# Swbot_shield.net
KiCad netlist of a schematic drawn in EAGLE
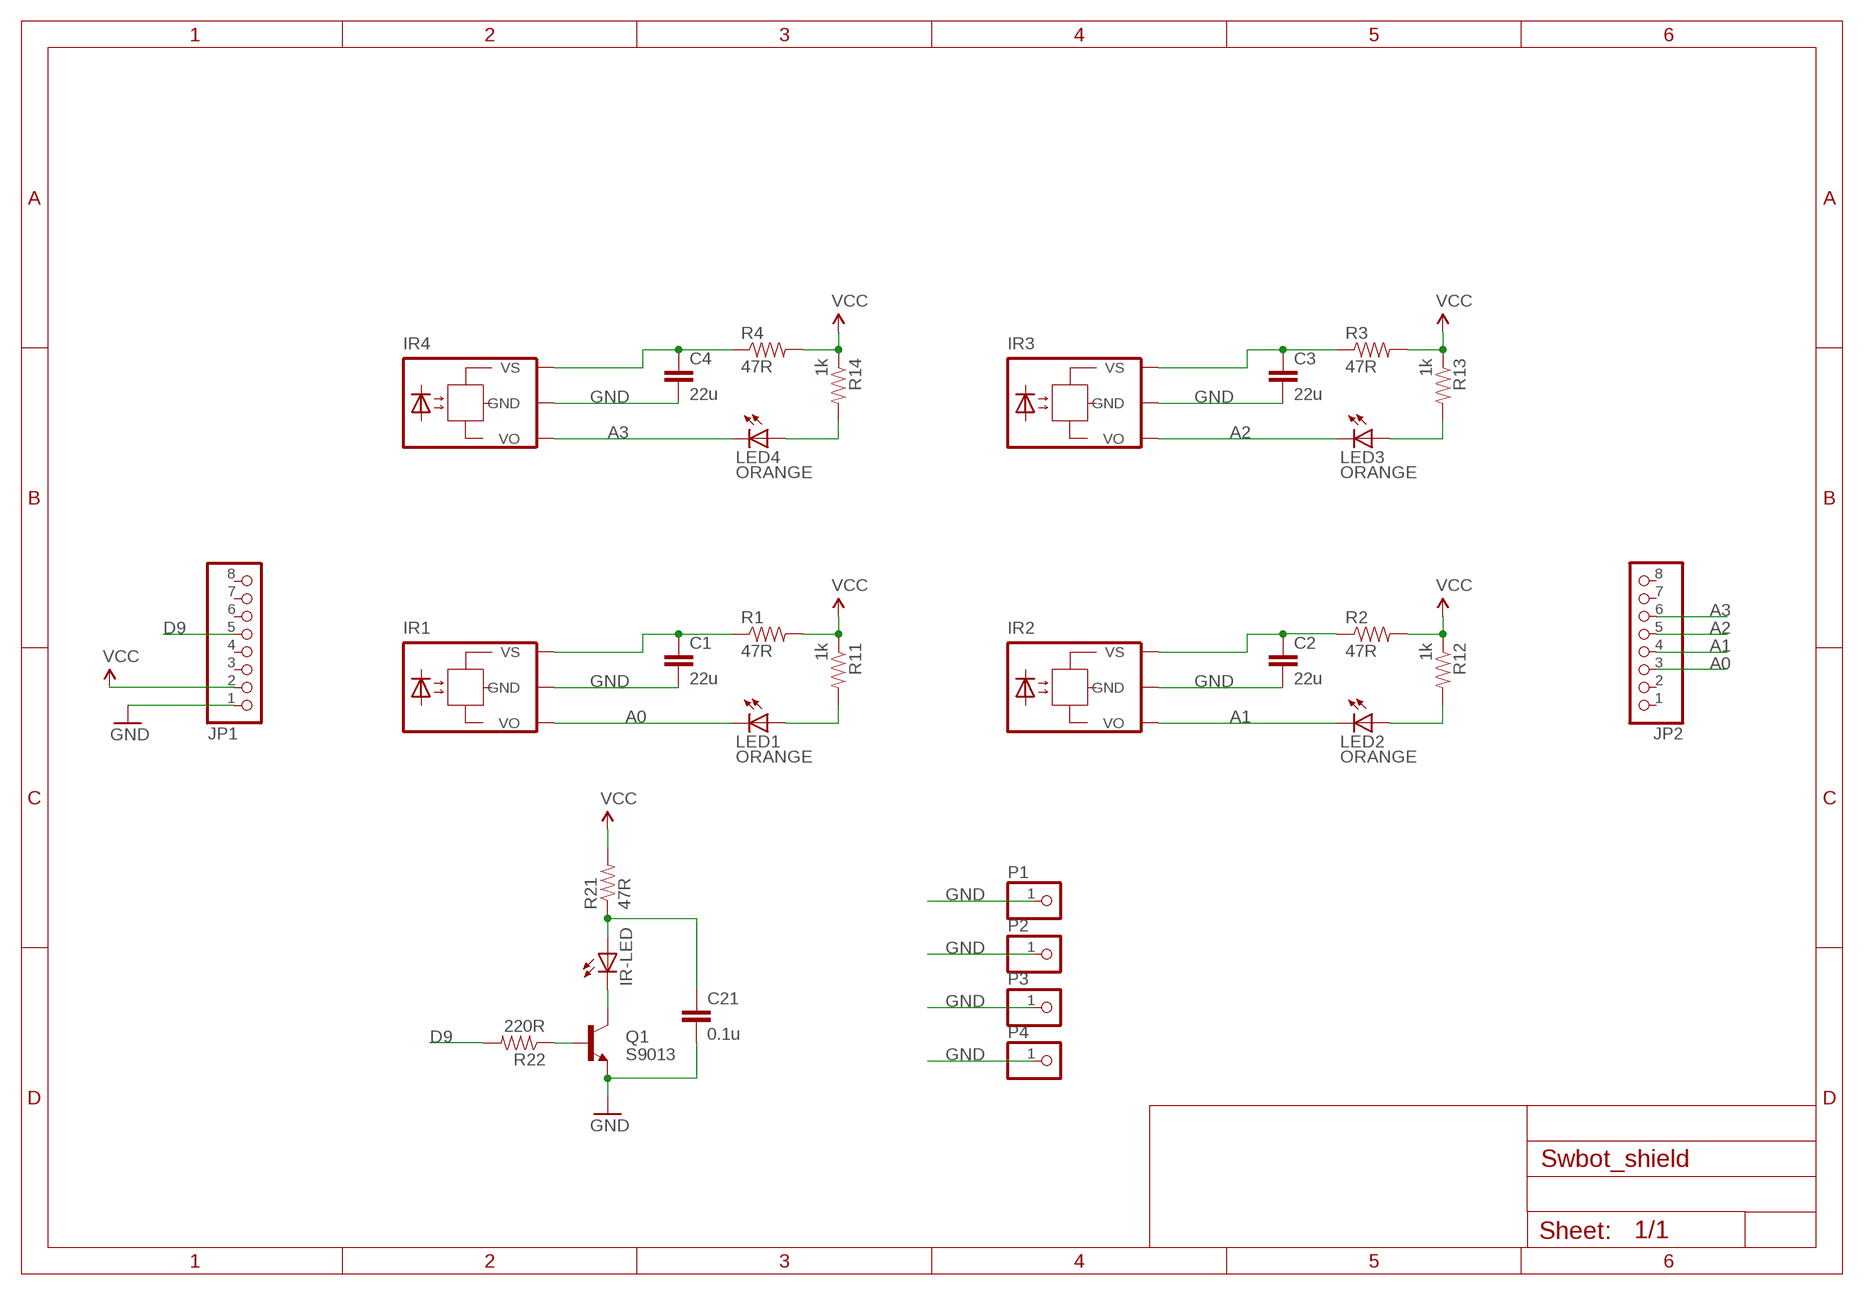
[diagram p0: schematic, sheet 1]

(export (version "E")
  (design (tool "Eeschema 10.0.6"))
  (components
    (comp (ref "C1")
      (value "22u")
      (footprint "eagle-import:1206")
      (libsource (lib "eagle-import") (part "CAP1206"))
    )
    (comp (ref "C2")
      (value "22u")
      (footprint "eagle-import:1206")
      (libsource (lib "eagle-import") (part "CAP1206"))
    )
    (comp (ref "C3")
      (value "22u")
      (footprint "eagle-import:1206")
      (libsource (lib "eagle-import") (part "CAP1206"))
    )
    (comp (ref "C4")
      (value "22u")
      (footprint "eagle-import:1206")
      (libsource (lib "eagle-import") (part "CAP1206"))
    )
    (comp (ref "C21")
      (value "0.1u")
      (footprint "eagle-import:0805")
      (libsource (lib "eagle-import") (part "CAP0805"))
    )
    (comp (ref "IR-LED")
      (value "LED5MM")
      (footprint "eagle-import:LED5MM")
      (libsource (lib "eagle-import") (part "LED5MM"))
    )
    (comp (ref "IR1")
      (value "-NJL")
      (footprint "eagle-import:TSOP")
      (libsource (lib "eagle-import") (part "?-NJL"))
    )
    (comp (ref "IR2")
      (value "-NJL")
      (footprint "eagle-import:TSOP")
      (libsource (lib "eagle-import") (part "?-NJL"))
    )
    (comp (ref "IR3")
      (value "-NJL")
      (footprint "eagle-import:TSOP")
      (libsource (lib "eagle-import") (part "?-NJL"))
    )
    (comp (ref "IR4")
      (value "-NJL")
      (footprint "eagle-import:TSOP")
      (libsource (lib "eagle-import") (part "?-NJL"))
    )
    (comp (ref "JP1")
      (value "PINHD-1X8")
      (footprint "eagle-import:1X08")
      (libsource (lib "eagle-import") (part "PINHD-1X8"))
    )
    (comp (ref "JP2")
      (value "PINHD-1X8")
      (footprint "eagle-import:1X08")
      (libsource (lib "eagle-import") (part "PINHD-1X8"))
    )
    (comp (ref "LED1")
      (value "ORANGE")
      (footprint "eagle-import:CHIPLED_0805")
      (libsource (lib "eagle-import") (part "LEDCHIPLED_0805"))
    )
    (comp (ref "LED2")
      (value "ORANGE")
      (footprint "eagle-import:CHIPLED_0805")
      (libsource (lib "eagle-import") (part "LEDCHIPLED_0805"))
    )
    (comp (ref "LED3")
      (value "ORANGE")
      (footprint "eagle-import:CHIPLED_0805")
      (libsource (lib "eagle-import") (part "LEDCHIPLED_0805"))
    )
    (comp (ref "LED4")
      (value "ORANGE")
      (footprint "eagle-import:CHIPLED_0805")
      (libsource (lib "eagle-import") (part "LEDCHIPLED_0805"))
    )
    (comp (ref "P1")
      (value "PINHD-1X1")
      (footprint "eagle-import:1X01")
      (libsource (lib "eagle-import") (part "PINHD-1X1"))
    )
    (comp (ref "P2")
      (value "PINHD-1X1")
      (footprint "eagle-import:1X01")
      (libsource (lib "eagle-import") (part "PINHD-1X1"))
    )
    (comp (ref "P3")
      (value "PINHD-1X1")
      (footprint "eagle-import:1X01")
      (libsource (lib "eagle-import") (part "PINHD-1X1"))
    )
    (comp (ref "P4")
      (value "PINHD-1X1")
      (footprint "eagle-import:1X01")
      (libsource (lib "eagle-import") (part "PINHD-1X1"))
    )
    (comp (ref "Q1")
      (value "S9013")
      (footprint "eagle-import:SOT23-3")
      (libsource (lib "eagle-import") (part "TRANSISTOR_NPNSOT23-3"))
    )
    (comp (ref "R1")
      (value "47R")
      (footprint "eagle-import:0805")
      (libsource (lib "eagle-import") (part "RESISTOR0805-RES"))
    )
    (comp (ref "R2")
      (value "47R")
      (footprint "eagle-import:0805")
      (libsource (lib "eagle-import") (part "RESISTOR0805-RES"))
    )
    (comp (ref "R3")
      (value "47R")
      (footprint "eagle-import:0805")
      (libsource (lib "eagle-import") (part "RESISTOR0805-RES"))
    )
    (comp (ref "R4")
      (value "47R")
      (footprint "eagle-import:0805")
      (libsource (lib "eagle-import") (part "RESISTOR0805-RES"))
    )
    (comp (ref "R11")
      (value "1k")
      (footprint "eagle-import:0805")
      (libsource (lib "eagle-import") (part "RESISTOR0805-RES"))
    )
    (comp (ref "R12")
      (value "1k")
      (footprint "eagle-import:0805")
      (libsource (lib "eagle-import") (part "RESISTOR0805-RES"))
    )
    (comp (ref "R13")
      (value "1k")
      (footprint "eagle-import:0805")
      (libsource (lib "eagle-import") (part "RESISTOR0805-RES"))
    )
    (comp (ref "R14")
      (value "1k")
      (footprint "eagle-import:0805")
      (libsource (lib "eagle-import") (part "RESISTOR0805-RES"))
    )
    (comp (ref "R21")
      (value "47R")
      (footprint "eagle-import:0805")
      (libsource (lib "eagle-import") (part "RESISTOR0805-RES"))
    )
    (comp (ref "R22")
      (value "220R")
      (footprint "eagle-import:0805")
      (libsource (lib "eagle-import") (part "RESISTOR0805-RES"))
    )
  )
  (nets
    (net (code "1") (name "/A0") (class "Default")
      (node (ref "IR1") (pin "VO") (pinfunction "VO_VO") (pintype "open_collector"))
      (node (ref "JP2") (pin "3") (pinfunction "3_3") (pintype "passive"))
      (node (ref "LED1") (pin "C") (pinfunction "C_C") (pintype "passive"))
    )
    (net (code "2") (name "/A1") (class "Default")
      (node (ref "IR2") (pin "VO") (pinfunction "VO_VO") (pintype "open_collector"))
      (node (ref "JP2") (pin "4") (pinfunction "4_4") (pintype "passive"))
      (node (ref "LED2") (pin "C") (pinfunction "C_C") (pintype "passive"))
    )
    (net (code "3") (name "/A2") (class "Default")
      (node (ref "IR3") (pin "VO") (pinfunction "VO_VO") (pintype "open_collector"))
      (node (ref "JP2") (pin "5") (pinfunction "5_5") (pintype "passive"))
      (node (ref "LED3") (pin "C") (pinfunction "C_C") (pintype "passive"))
    )
    (net (code "4") (name "/A3") (class "Default")
      (node (ref "IR4") (pin "VO") (pinfunction "VO_VO") (pintype "open_collector"))
      (node (ref "JP2") (pin "6") (pinfunction "6_6") (pintype "passive"))
      (node (ref "LED4") (pin "C") (pinfunction "C_C") (pintype "passive"))
    )
    (net (code "5") (name "/D9") (class "Default")
      (node (ref "JP1") (pin "5") (pinfunction "5_5") (pintype "passive"))
      (node (ref "R22") (pin "2") (pinfunction "2_2") (pintype "passive"))
    )
    (net (code "6") (name "GND") (class "Default")
      (node (ref "C1") (pin "2") (pinfunction "2_2") (pintype "passive"))
      (node (ref "C2") (pin "2") (pinfunction "2_2") (pintype "passive"))
      (node (ref "C21") (pin "2") (pinfunction "2_2") (pintype "passive"))
      (node (ref "C3") (pin "2") (pinfunction "2_2") (pintype "passive"))
      (node (ref "C4") (pin "2") (pinfunction "2_2") (pintype "passive"))
      (node (ref "IR1") (pin "GND") (pinfunction "GND_GND") (pintype "power_in"))
      (node (ref "IR2") (pin "GND") (pinfunction "GND_GND") (pintype "power_in"))
      (node (ref "IR3") (pin "GND") (pinfunction "GND_GND") (pintype "power_in"))
      (node (ref "IR4") (pin "GND") (pinfunction "GND_GND") (pintype "power_in"))
      (node (ref "JP1") (pin "1") (pinfunction "1_1") (pintype "passive"))
      (node (ref "P1") (pin "1") (pinfunction "1_1") (pintype "passive"))
      (node (ref "P2") (pin "1") (pinfunction "1_1") (pintype "passive"))
      (node (ref "P3") (pin "1") (pinfunction "1_1") (pintype "passive"))
      (node (ref "P4") (pin "1") (pinfunction "1_1") (pintype "passive"))
      (node (ref "Q1") (pin "2") (pinfunction "E_2") (pintype "passive"))
    )
    (net (code "7") (name "Net-(C21-Pad1)") (class "Default")
      (node (ref "C21") (pin "1") (pinfunction "1_1") (pintype "passive"))
      (node (ref "IR-LED") (pin "A") (pinfunction "A_A") (pintype "passive"))
      (node (ref "R21") (pin "1") (pinfunction "1_1") (pintype "passive"))
    )
    (net (code "8") (name "Net-(IR-LED-C)") (class "Default")
      (node (ref "IR-LED") (pin "K") (pinfunction "C_K") (pintype "passive"))
      (node (ref "Q1") (pin "3") (pinfunction "C_3") (pintype "passive"))
    )
    (net (code "9") (name "Net-(IR1-VS)") (class "Default")
      (node (ref "C1") (pin "1") (pinfunction "1_1") (pintype "passive"))
      (node (ref "IR1") (pin "VCC") (pinfunction "VS_VCC") (pintype "power_in"))
      (node (ref "R1") (pin "1") (pinfunction "1_1") (pintype "passive"))
    )
    (net (code "10") (name "Net-(IR2-VS)") (class "Default")
      (node (ref "C2") (pin "1") (pinfunction "1_1") (pintype "passive"))
      (node (ref "IR2") (pin "VCC") (pinfunction "VS_VCC") (pintype "power_in"))
      (node (ref "R2") (pin "1") (pinfunction "1_1") (pintype "passive"))
    )
    (net (code "11") (name "Net-(IR3-VS)") (class "Default")
      (node (ref "C3") (pin "1") (pinfunction "1_1") (pintype "passive"))
      (node (ref "IR3") (pin "VCC") (pinfunction "VS_VCC") (pintype "power_in"))
      (node (ref "R3") (pin "1") (pinfunction "1_1") (pintype "passive"))
    )
    (net (code "12") (name "Net-(IR4-VS)") (class "Default")
      (node (ref "C4") (pin "1") (pinfunction "1_1") (pintype "passive"))
      (node (ref "IR4") (pin "VCC") (pinfunction "VS_VCC") (pintype "power_in"))
      (node (ref "R4") (pin "1") (pinfunction "1_1") (pintype "passive"))
    )
    (net (code "13") (name "Net-(LED1-PadA)") (class "Default")
      (node (ref "LED1") (pin "A") (pinfunction "A_A") (pintype "passive"))
      (node (ref "R11") (pin "2") (pinfunction "2_2") (pintype "passive"))
    )
    (net (code "14") (name "Net-(LED2-PadA)") (class "Default")
      (node (ref "LED2") (pin "A") (pinfunction "A_A") (pintype "passive"))
      (node (ref "R12") (pin "2") (pinfunction "2_2") (pintype "passive"))
    )
    (net (code "15") (name "Net-(LED3-PadA)") (class "Default")
      (node (ref "LED3") (pin "A") (pinfunction "A_A") (pintype "passive"))
      (node (ref "R13") (pin "2") (pinfunction "2_2") (pintype "passive"))
    )
    (net (code "16") (name "Net-(LED4-PadA)") (class "Default")
      (node (ref "LED4") (pin "A") (pinfunction "A_A") (pintype "passive"))
      (node (ref "R14") (pin "2") (pinfunction "2_2") (pintype "passive"))
    )
    (net (code "17") (name "Net-(Q1-B)") (class "Default")
      (node (ref "Q1") (pin "1") (pinfunction "B_1") (pintype "passive"))
      (node (ref "R22") (pin "1") (pinfunction "1_1") (pintype "passive"))
    )
    (net (code "18") (name "VCC") (class "Default")
      (node (ref "JP1") (pin "2") (pinfunction "2_2") (pintype "passive"))
      (node (ref "R1") (pin "2") (pinfunction "2_2") (pintype "passive"))
      (node (ref "R11") (pin "1") (pinfunction "1_1") (pintype "passive"))
      (node (ref "R12") (pin "1") (pinfunction "1_1") (pintype "passive"))
      (node (ref "R13") (pin "1") (pinfunction "1_1") (pintype "passive"))
      (node (ref "R14") (pin "1") (pinfunction "1_1") (pintype "passive"))
      (node (ref "R2") (pin "2") (pinfunction "2_2") (pintype "passive"))
      (node (ref "R21") (pin "2") (pinfunction "2_2") (pintype "passive"))
      (node (ref "R3") (pin "2") (pinfunction "2_2") (pintype "passive"))
      (node (ref "R4") (pin "2") (pinfunction "2_2") (pintype "passive"))
    )
    (net (code "19") (name "unconnected-(JP1-Pad3)") (class "Default")
      (node (ref "JP1") (pin "3") (pinfunction "3_3") (pintype "passive"))
    )
    (net (code "20") (name "unconnected-(JP1-Pad4)") (class "Default")
      (node (ref "JP1") (pin "4") (pinfunction "4_4") (pintype "passive"))
    )
    (net (code "21") (name "unconnected-(JP1-Pad6)") (class "Default")
      (node (ref "JP1") (pin "6") (pinfunction "6_6") (pintype "passive"))
    )
    (net (code "22") (name "unconnected-(JP1-Pad7)") (class "Default")
      (node (ref "JP1") (pin "7") (pinfunction "7_7") (pintype "passive"))
    )
    (net (code "23") (name "unconnected-(JP1-Pad8)") (class "Default")
      (node (ref "JP1") (pin "8") (pinfunction "8_8") (pintype "passive"))
    )
    (net (code "24") (name "unconnected-(JP2-Pad1)") (class "Default")
      (node (ref "JP2") (pin "1") (pinfunction "1_1") (pintype "passive"))
    )
    (net (code "25") (name "unconnected-(JP2-Pad2)") (class "Default")
      (node (ref "JP2") (pin "2") (pinfunction "2_2") (pintype "passive"))
    )
    (net (code "26") (name "unconnected-(JP2-Pad7)") (class "Default")
      (node (ref "JP2") (pin "7") (pinfunction "7_7") (pintype "passive"))
    )
    (net (code "27") (name "unconnected-(JP2-Pad8)") (class "Default")
      (node (ref "JP2") (pin "8") (pinfunction "8_8") (pintype "passive"))
    )
  )
)
